# Accumulator_Indicator_Light_r2.net
KiCad netlist of a schematic drawn in EAGLE
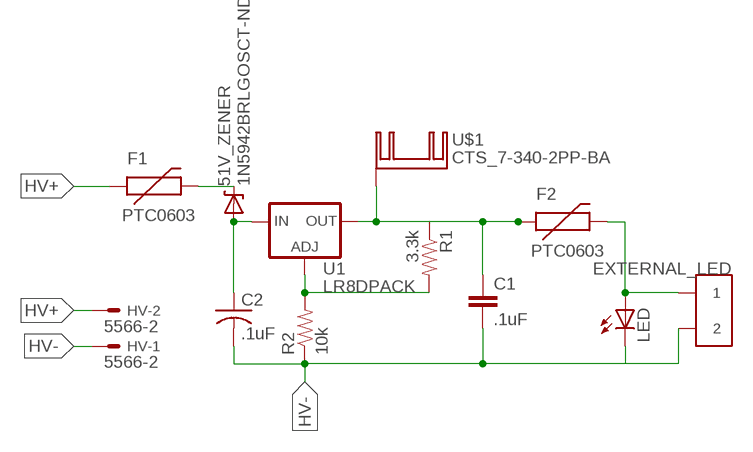
[diagram p0: schematic, sheet 1]

(export (version "E")
  (design (tool "Eeschema 10.0.6"))
  (components
    (comp (ref "51V_ZENER")
      (value "1N5942BRLGOSCT-ND")
      (footprint "eagle-import:DIODE-ZENER")
      (libsource (lib "eagle-import") (part "DIODE-ZENERPTH"))
    )
    (comp (ref "C1")
      (value ".1uF")
      (footprint "eagle-import:0603-CAP")
      (libsource (lib "eagle-import") (part "CAP0603-CAP"))
    )
    (comp (ref "C2")
      (value ".1uF")
      (footprint "eagle-import:C2220")
      (libsource (lib "eagle-import") (part "C-USC2220"))
    )
    (comp (ref "EXTERNAL_LED")
      (value "CONN_2")
      (footprint "eagle-import:CONNECTOR_2")
      (libsource (lib "eagle-import") (part "CONN_2"))
    )
    (comp (ref "F1")
      (value "PTC0603")
      (footprint "eagle-import:0603")
      (libsource (lib "eagle-import") (part "PTC0603"))
    )
    (comp (ref "F2")
      (value "PTC0603")
      (footprint "eagle-import:0603")
      (libsource (lib "eagle-import") (part "PTC0603"))
    )
    (comp (ref "HV")
      (value "5566-2")
      (footprint "eagle-import:5566-2")
      (libsource (lib "eagle-import") (part "5566-2"))
    )
    (comp (ref "LED")
      (value "LEDSMT1206")
      (footprint "eagle-import:1206")
      (libsource (lib "eagle-import") (part "LEDSMT1206"))
    )
    (comp (ref "R1")
      (value "3.3k")
      (footprint "eagle-import:0603-RES")
      (libsource (lib "eagle-import") (part "RESISTOR0603"))
    )
    (comp (ref "R2")
      (value "10k")
      (footprint "eagle-import:0603-RES")
      (libsource (lib "eagle-import") (part "RESISTOR0603"))
    )
    (comp (ref "U$1")
      (value "CTS_7-340-2PP-BA")
      (footprint "eagle-import:TO-200_DUAL")
      (libsource (lib "eagle-import") (part "CTS_7-340-2PP-BA"))
    )
    (comp (ref "U1")
      (value "LR8DPACK")
      (footprint "eagle-import:DPACK")
      (libsource (lib "eagle-import") (part "LR8DPACK"))
    )
  )
  (nets
    (net (code "1") (name "HV+") (class "Default")
      (node (ref "F1") (pin "1") (pinfunction "1_1") (pintype "bidirectional"))
      (node (ref "HV") (pin "2") (pinfunction "S_2") (pintype "passive"))
    )
    (net (code "2") (name "HV-") (class "Default")
      (node (ref "C1") (pin "2") (pinfunction "2_2") (pintype "passive"))
      (node (ref "C2") (pin "2") (pinfunction "2_2") (pintype "passive"))
      (node (ref "EXTERNAL_LED") (pin "3") (pinfunction "2_3") (pintype "bidirectional"))
      (node (ref "EXTERNAL_LED") (pin "4") (pinfunction "2_4") (pintype "bidirectional"))
      (node (ref "HV") (pin "1") (pinfunction "S_1") (pintype "passive"))
      (node (ref "LED") (pin "C") (pinfunction "C_C") (pintype "passive"))
      (node (ref "R2") (pin "1") (pinfunction "1_1") (pintype "passive"))
    )
    (net (code "3") (name "Net-(51V_ZENER-A)") (class "Default")
      (node (ref "51V_ZENER") (pin "P$2") (pinfunction "A_P$2") (pintype "passive"))
      (node (ref "C2") (pin "1") (pinfunction "1_1") (pintype "passive"))
      (node (ref "U1") (pin "1") (pinfunction "IN_1") (pintype "input"))
    )
    (net (code "4") (name "Net-(51V_ZENER-C)") (class "Default")
      (node (ref "51V_ZENER") (pin "P$1") (pinfunction "C_P$1") (pintype "passive"))
      (node (ref "F1") (pin "2") (pinfunction "2_2") (pintype "bidirectional"))
    )
    (net (code "5") (name "Net-(EXTERNAL_LED-1-Pad2)") (class "Default")
      (node (ref "EXTERNAL_LED") (pin "1") (pinfunction "1_1") (pintype "bidirectional"))
      (node (ref "EXTERNAL_LED") (pin "2") (pinfunction "1_2") (pintype "bidirectional"))
      (node (ref "F2") (pin "2") (pinfunction "2_2") (pintype "bidirectional"))
      (node (ref "LED") (pin "A") (pinfunction "A_A") (pintype "passive"))
    )
    (net (code "6") (name "Net-(U1-ADJ)") (class "Default")
      (node (ref "R1") (pin "2") (pinfunction "2_2") (pintype "passive"))
      (node (ref "R2") (pin "2") (pinfunction "2_2") (pintype "passive"))
      (node (ref "U1") (pin "3") (pinfunction "ADJ_3") (pintype "input"))
    )
    (net (code "7") (name "Net-(U1-OUT)") (class "Default")
      (node (ref "C1") (pin "1") (pinfunction "1_1") (pintype "passive"))
      (node (ref "F2") (pin "1") (pinfunction "1_1") (pintype "bidirectional"))
      (node (ref "R1") (pin "1") (pinfunction "1_1") (pintype "passive"))
      (node (ref "U$1") (pin "P$1") (pinfunction "K_P$1") (pintype "passive"))
      (node (ref "U$1") (pin "P$2") (pinfunction "K_P$2") (pintype "passive"))
      (node (ref "U$1") (pin "P$3") (pinfunction "K_P$3") (pintype "passive"))
      (node (ref "U1") (pin "4") (pinfunction "OUT_4") (pintype "passive"))
    )
  )
)
